# COMM.net
KiCad netlist of a schematic drawn in Altium Designer
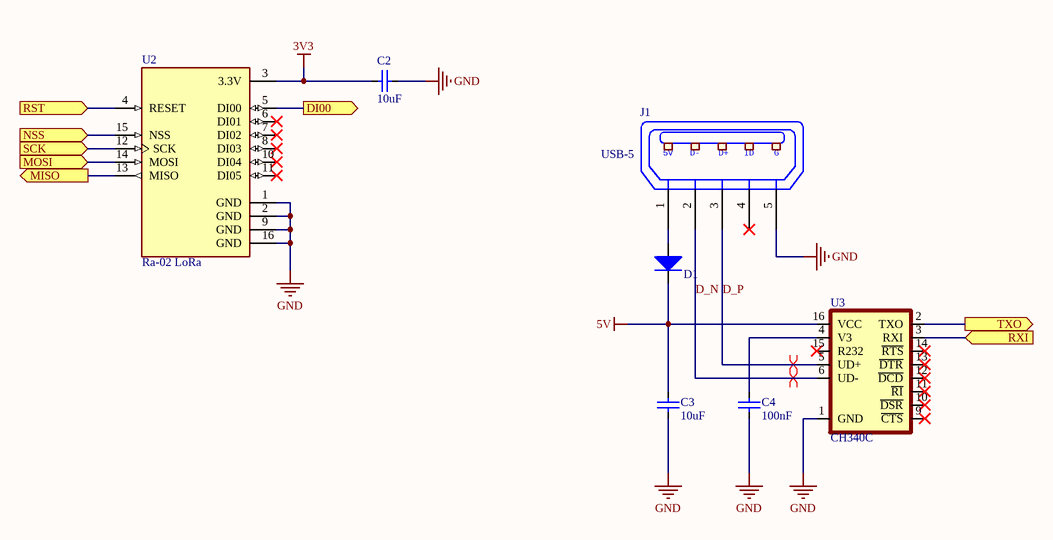
[diagram p0: COMM.SchDoc]

(export (version "E")
  (design (tool "Eeschema 10.0.6"))
  (components
    (comp (ref "C2")
      (value "10uF")
      (footprint "CAP_0805")
      (description "Capacitor")
      (fields (field (name "PUBLISHER") "Altium Limited"))
      (libsource (lib "My Library") (part "CapSMD"))
    )
    (comp (ref "C3")
      (value "10uF")
      (footprint "CAP_0805")
      (description "Capacitor")
      (fields (field (name "PUBLISHER") "Altium Limited"))
      (libsource (lib "My Library") (part "CapSMD"))
    )
    (comp (ref "C4")
      (value "100nF")
      (footprint "CAP_0805")
      (description "Capacitor")
      (fields (field (name "PUBLISHER") "Altium Limited"))
      (libsource (lib "My Library") (part "CapSMD"))
    )
    (comp (ref "D1")
      (value "Diode SMD")
      (footprint "DIO-214AC(SMA)")
      (description "Default Diode")
      (fields (field (name "PUBLISHER") "Altium Limited"))
      (libsource (lib "My Library") (part "Diode SMD"))
    )
    (comp (ref "J1")
      (value "USB-5")
      (footprint "USB-M1")
      (fields
        (field (name "MANUFACTURER") "FCI")
        (field (name "MANUFACTURER PART NUMBER") "10118193-0001LF")
        (field (name ".CREATOR") "MM")
        (field (name ".CHECKED PCB") "RF")
        (field (name ".CHECKED SCH") "MM")
      )
      (libsource (lib "My Library") (part "USB-5"))
    )
    (comp (ref "U2")
      (value "Ra-02 LoRa")
      (footprint "Ra-02")
      (description "LoRa Module Ra-02")
      (libsource (lib "My Library") (part "Ra-02 LoRa"))
    )
    (comp (ref "U3")
      (value "CH340C")
      (footprint "SOP-16")
      (description "USB to serial chip CH340")
      (fields (field (name "MF") "WCH"))
      (libsource (lib "My Library") (part "CH340C"))
    )
  )
  (nets
    (net (code "1") (name "/DI00") (class "Default")
      (node (ref "U2") (pin "5") (pinfunction "DI00_5") (pintype "bidirectional"))
    )
    (net (code "2") (name "/D_N") (class "Default")
      (node (ref "J1") (pin "2") (pinfunction "P2_2") (pintype "passive"))
      (node (ref "U3") (pin "6") (pinfunction "UD-_6") (pintype "bidirectional"))
    )
    (net (code "3") (name "/D_P") (class "Default")
      (node (ref "J1") (pin "3") (pinfunction "P3_3") (pintype "passive"))
      (node (ref "U3") (pin "5") (pinfunction "UD+_5") (pintype "bidirectional"))
    )
    (net (code "4") (name "/MISO") (class "Default")
      (node (ref "U2") (pin "13") (pinfunction "MISO_13") (pintype "output"))
    )
    (net (code "5") (name "/MOSI") (class "Default")
      (node (ref "U2") (pin "14") (pinfunction "MOSI_14") (pintype "input"))
    )
    (net (code "6") (name "/NSS") (class "Default")
      (node (ref "U2") (pin "15") (pinfunction "NSS_15") (pintype "input"))
    )
    (net (code "7") (name "/RST") (class "Default")
      (node (ref "U2") (pin "4") (pinfunction "RESET_4") (pintype "input"))
    )
    (net (code "8") (name "/RXI") (class "Default")
      (node (ref "U3") (pin "3") (pinfunction "RXI_3") (pintype "bidirectional"))
    )
    (net (code "9") (name "/SCK") (class "Default")
      (node (ref "U2") (pin "12") (pinfunction "SCK_12") (pintype "input"))
    )
    (net (code "10") (name "/TXO") (class "Default")
      (node (ref "U3") (pin "2") (pinfunction "TXO_2") (pintype "bidirectional"))
    )
    (net (code "11") (name "3V3") (class "Default")
      (node (ref "C2") (pin "2") (pinfunction "2_2") (pintype "passive"))
      (node (ref "U2") (pin "3") (pinfunction "3.3V_3") (pintype "power_in"))
    )
    (net (code "12") (name "5V") (class "Default")
      (node (ref "C3") (pin "2") (pinfunction "2_2") (pintype "passive"))
      (node (ref "D1") (pin "2") (pinfunction "K_2") (pintype "passive"))
      (node (ref "U3") (pin "16") (pinfunction "VCC_16") (pintype "bidirectional"))
    )
    (net (code "13") (name "GND") (class "Default")
      (node (ref "C2") (pin "1") (pinfunction "1_1") (pintype "passive"))
      (node (ref "C3") (pin "1") (pinfunction "1_1") (pintype "passive"))
      (node (ref "C4") (pin "1") (pinfunction "1_1") (pintype "passive"))
      (node (ref "J1") (pin "5") (pinfunction "P5_5") (pintype "passive"))
      (node (ref "U2") (pin "1") (pinfunction "GND_1") (pintype "power_in"))
      (node (ref "U2") (pin "16") (pinfunction "GND_16") (pintype "power_in"))
      (node (ref "U2") (pin "2") (pinfunction "GND_2") (pintype "power_in"))
      (node (ref "U2") (pin "9") (pinfunction "GND_9") (pintype "power_in"))
      (node (ref "U3") (pin "1") (pinfunction "GND_1") (pintype "bidirectional"))
    )
    (net (code "14") (name "Net-(D1-A)") (class "Default")
      (node (ref "D1") (pin "1") (pinfunction "A_1") (pintype "passive"))
      (node (ref "J1") (pin "1") (pinfunction "P1_1") (pintype "passive"))
    )
    (net (code "15") (name "Net-(U3-V3)") (class "Default")
      (node (ref "C4") (pin "2") (pinfunction "2_2") (pintype "passive"))
      (node (ref "U3") (pin "4") (pinfunction "V3_4") (pintype "bidirectional"))
    )
    (net (code "16") (name "unconnected-(J1-P4-Pad4)") (class "Default")
      (node (ref "J1") (pin "4") (pinfunction "P4_4") (pintype "passive+no_connect"))
    )
    (net (code "17") (name "unconnected-(U2-DI01-Pad6)") (class "Default")
      (node (ref "U2") (pin "6") (pinfunction "DI01_6") (pintype "bidirectional+no_connect"))
    )
    (net (code "18") (name "unconnected-(U2-DI02-Pad7)") (class "Default")
      (node (ref "U2") (pin "7") (pinfunction "DI02_7") (pintype "bidirectional+no_connect"))
    )
    (net (code "19") (name "unconnected-(U2-DI03-Pad8)") (class "Default")
      (node (ref "U2") (pin "8") (pinfunction "DI03_8") (pintype "bidirectional+no_connect"))
    )
    (net (code "20") (name "unconnected-(U2-DI04-Pad10)") (class "Default")
      (node (ref "U2") (pin "10") (pinfunction "DI04_10") (pintype "bidirectional+no_connect"))
    )
    (net (code "21") (name "unconnected-(U2-DI05-Pad11)") (class "Default")
      (node (ref "U2") (pin "11") (pinfunction "DI05_11") (pintype "bidirectional+no_connect"))
    )
    (net (code "22") (name "unconnected-(U3-R232-Pad15)") (class "Default")
      (node (ref "U3") (pin "15") (pinfunction "R232_15") (pintype "bidirectional+no_connect"))
    )
    (net (code "23") (name "unconnected-(U3-~{CTS}-Pad9)") (class "Default")
      (node (ref "U3") (pin "9") (pinfunction "~{CTS}_9") (pintype "bidirectional+no_connect"))
    )
    (net (code "24") (name "unconnected-(U3-~{DCD}-Pad12)") (class "Default")
      (node (ref "U3") (pin "12") (pinfunction "~{DCD}_12") (pintype "bidirectional+no_connect"))
    )
    (net (code "25") (name "unconnected-(U3-~{DSR}-Pad10)") (class "Default")
      (node (ref "U3") (pin "10") (pinfunction "~{DSR}_10") (pintype "bidirectional+no_connect"))
    )
    (net (code "26") (name "unconnected-(U3-~{DTR}-Pad13)") (class "Default")
      (node (ref "U3") (pin "13") (pinfunction "~{DTR}_13") (pintype "bidirectional+no_connect"))
    )
    (net (code "27") (name "unconnected-(U3-~{RI}-Pad11)") (class "Default")
      (node (ref "U3") (pin "11") (pinfunction "~{RI}_11") (pintype "bidirectional+no_connect"))
    )
    (net (code "28") (name "unconnected-(U3-~{RTS}-Pad14)") (class "Default")
      (node (ref "U3") (pin "14") (pinfunction "~{RTS}_14") (pintype "bidirectional+no_connect"))
    )
  )
)
